# Top_Sheet.net
KiCad netlist of a schematic drawn in Altium Designer
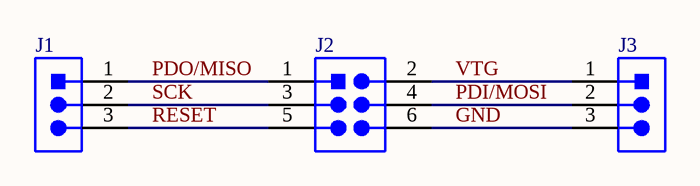
[diagram p0: Top Sheet.SchDoc]

(export (version "E")
  (design (tool "Eeschema 10.0.6"))
  (components
    (comp (ref "J1")
      (value "3 contacts Male header")
      (footprint "10129380-903001ALF")
      (description "Connector Male Header 1X3 vertical 3contacts 0.100in pitch Gold finish SMD")
      (fields (field (name "MANUFACTURER") "FCI"))
      (libsource (lib "") (part "Header 1X3_1"))
    )
    (comp (ref "J2")
      (value "AVR ICSP")
      (footprint "3020-06-0300-00 ICSP AVR ICE NEW")
      (description "AVR Serial ICSP, Shrouded, SMD - 6 Pin Shrouded Header, 0.100\", SMD")
      (fields (field (name "MANUFACTURER") "CNC Tech"))
      (libsource (lib "Connectors") (part "AVR ICSP"))
    )
    (comp (ref "J3")
      (value "3 contacts Male header")
      (footprint "10129380-903001ALF")
      (description "Connector Male Header 1X3 vertical 3contacts 0.100in pitch Gold finish SMD")
      (fields (field (name "MANUFACTURER") "FCI"))
      (libsource (lib "Connectors") (part "Header 1X3"))
    )
  )
  (nets
    (net (code "1") (name "/GND") (class "Default")
      (node (ref "J2") (pin "6") (pinfunction "GND_6") (pintype "power_in"))
      (node (ref "J3") (pin "3") (pinfunction "3_3") (pintype "passive"))
    )
    (net (code "2") (name "/PDI{slash}MOSI") (class "Default")
      (node (ref "J2") (pin "4") (pinfunction "PDI/MOSI_4") (pintype "passive"))
      (node (ref "J3") (pin "2") (pinfunction "2_2") (pintype "passive"))
    )
    (net (code "3") (name "/PDO{slash}MISO") (class "Default")
      (node (ref "J1") (pin "1") (pinfunction "1_1") (pintype "passive"))
      (node (ref "J2") (pin "1") (pinfunction "PDO/MISO_1") (pintype "passive"))
    )
    (net (code "4") (name "/RESET") (class "Default")
      (node (ref "J1") (pin "3") (pinfunction "3_3") (pintype "passive"))
      (node (ref "J2") (pin "5") (pinfunction "RESET_5") (pintype "passive"))
    )
    (net (code "5") (name "/SCK") (class "Default")
      (node (ref "J1") (pin "2") (pinfunction "2_2") (pintype "passive"))
      (node (ref "J2") (pin "3") (pinfunction "SCK_3") (pintype "passive"))
    )
    (net (code "6") (name "/VTG") (class "Default")
      (node (ref "J2") (pin "2") (pinfunction "VTG_(VCC)_2") (pintype "power_in"))
      (node (ref "J3") (pin "1") (pinfunction "1_1") (pintype "passive"))
    )
  )
)
